# 224_distance.net
KiCad netlist of a schematic drawn in EAGLE
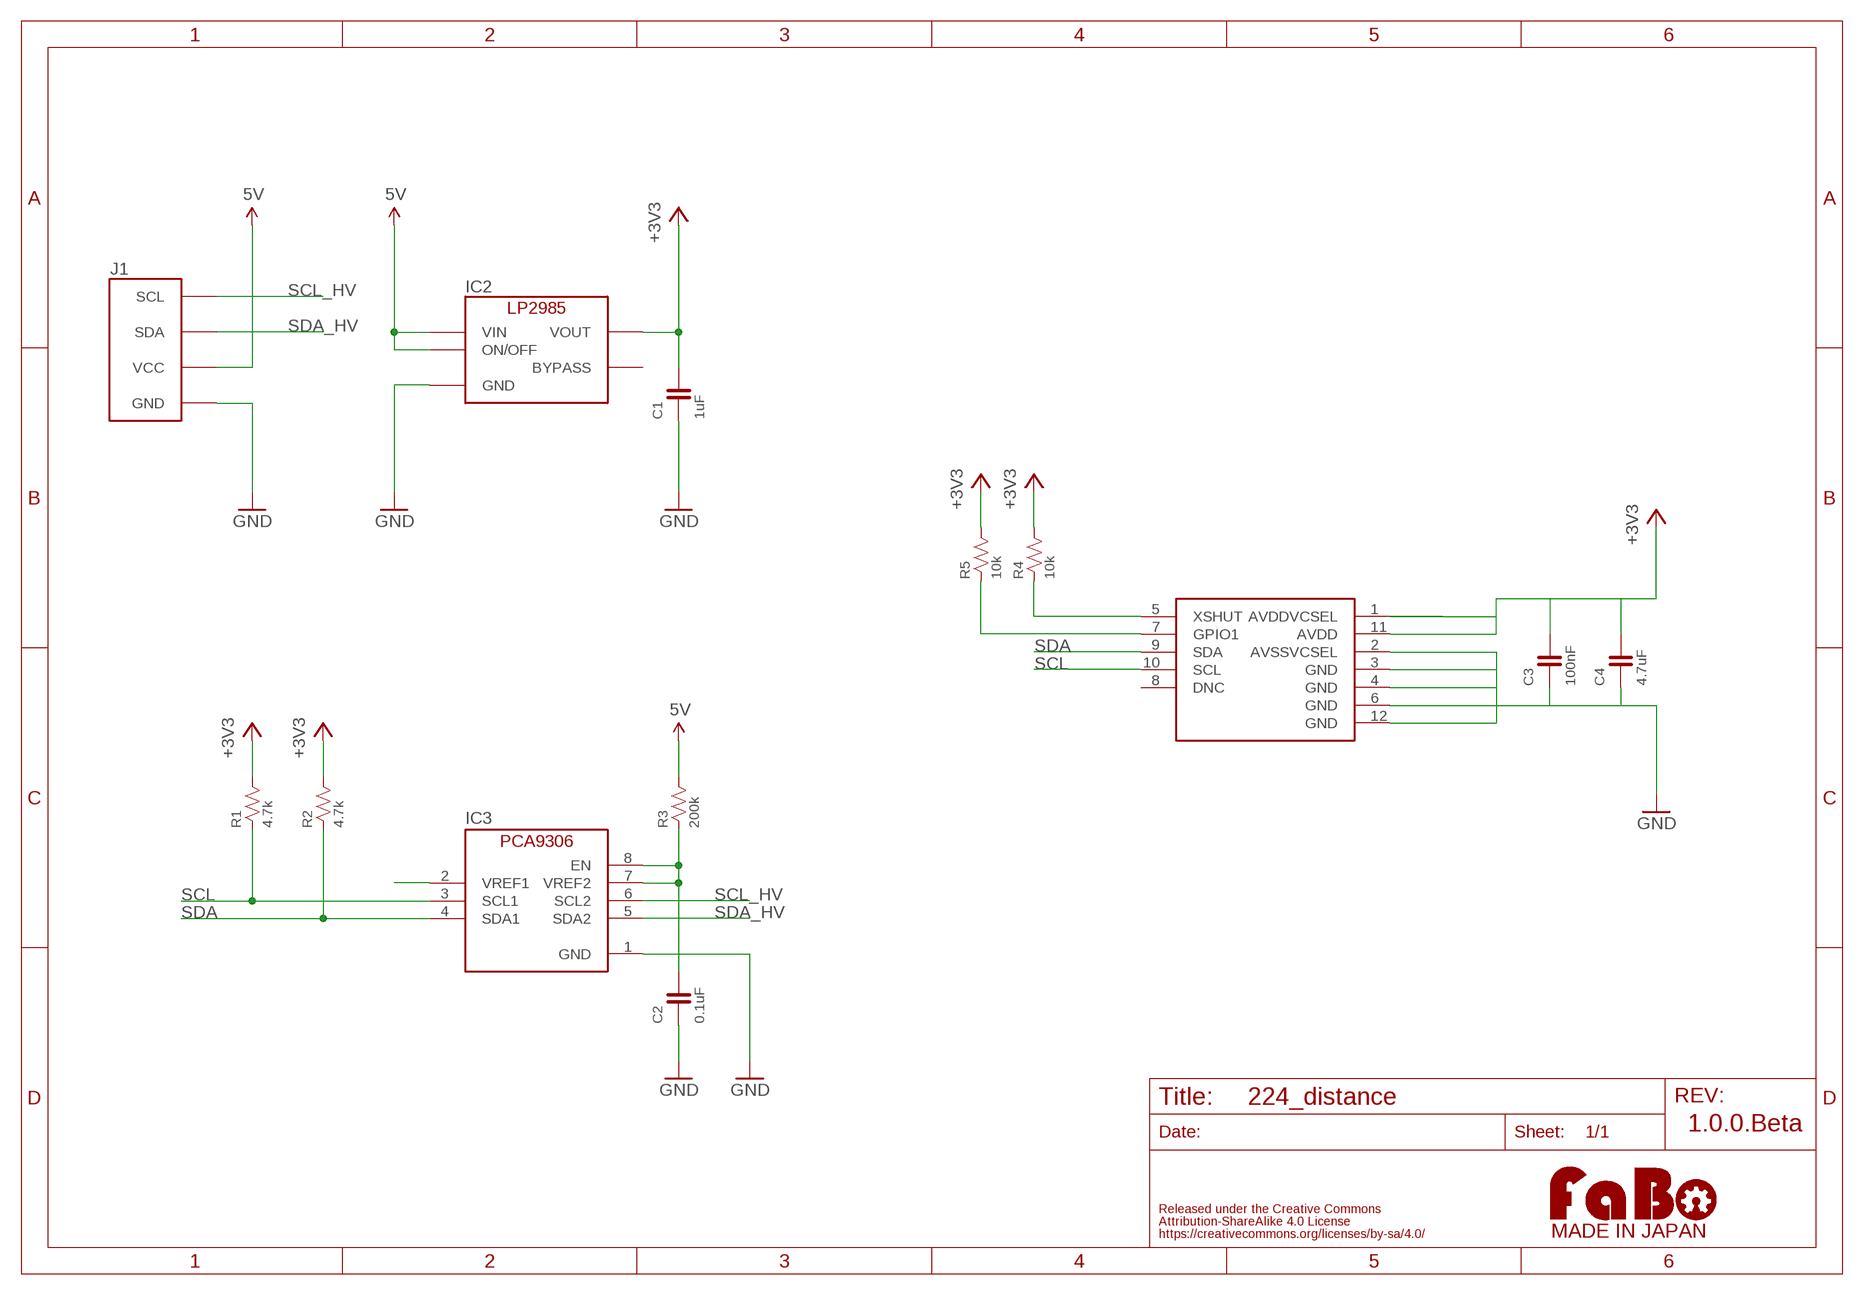
[diagram p0: schematic, sheet 1]

(export (version "E")
  (design (tool "Eeschema 10.0.6"))
  (components
    (comp (ref "C1")
      (value "1uF")
      (footprint "eagle-import:0603")
      (libsource (lib "eagle-import") (part "CAPACITOR-0603"))
    )
    (comp (ref "C2")
      (value "0.1uF")
      (footprint "eagle-import:0603")
      (libsource (lib "eagle-import") (part "CAPACITOR-0603"))
    )
    (comp (ref "C3")
      (value "100nF")
      (footprint "eagle-import:0603")
      (libsource (lib "eagle-import") (part "CAPACITOR-0603"))
    )
    (comp (ref "C4")
      (value "4.7uF")
      (footprint "eagle-import:0603")
      (libsource (lib "eagle-import") (part "CAPACITOR-0603"))
    )
    (comp (ref "IC2")
      (value "LP2985-33DBV")
      (footprint "eagle-import:SOT-23-5")
      (libsource (lib "eagle-import") (part "LP2985-33DBV"))
    )
    (comp (ref "IC3")
      (value "PCA9306GM")
      (footprint "eagle-import:XQFN8")
      (libsource (lib "eagle-import") (part "PCA9306GM"))
    )
    (comp (ref "J1")
      (value "FABO_BRICK_I2C-S04B-PASK-2")
      (footprint "eagle-import:FABO_BRICK_I2C_S04B-PASK-2")
      (libsource (lib "eagle-import") (part "FABO_BRICK_I2C-S04B-PASK-2"))
    )
    (comp (ref "R1")
      (value "4.7k")
      (footprint "eagle-import:0603")
      (libsource (lib "eagle-import") (part "RESISTOR-0603"))
    )
    (comp (ref "R2")
      (value "4.7k")
      (footprint "eagle-import:0603")
      (libsource (lib "eagle-import") (part "RESISTOR-0603"))
    )
    (comp (ref "R3")
      (value "200k")
      (footprint "eagle-import:0603")
      (libsource (lib "eagle-import") (part "RESISTOR-0603"))
    )
    (comp (ref "R4")
      (value "10k")
      (footprint "eagle-import:0603")
      (libsource (lib "eagle-import") (part "RESISTOR-0603"))
    )
    (comp (ref "R5")
      (value "10k")
      (footprint "eagle-import:0603")
      (libsource (lib "eagle-import") (part "RESISTOR-0603"))
    )
    (comp (ref "U$3")
      (value "LOGO_FABO-M")
      (footprint "eagle-import:LOGO_FABO_MS")
      (libsource (lib "eagle-import") (part "LOGO_FABO-M"))
    )
    (comp (ref "VL1")
      (value "ST-VL53L0XVL53")
      (footprint "eagle-import:ST-VL53L0X")
      (libsource (lib "eagle-import") (part "ST-VL53L0XVL53"))
    )
  )
  (nets
    (net (code "1") (name "+3V3") (class "Default")
      (node (ref "C1") (pin "2") (pinfunction "2_2") (pintype "passive"))
      (node (ref "C3") (pin "2") (pinfunction "2_2") (pintype "passive"))
      (node (ref "C4") (pin "2") (pinfunction "2_2") (pintype "passive"))
      (node (ref "IC2") (pin "5") (pinfunction "VOUT_5") (pintype "output"))
      (node (ref "R1") (pin "2") (pinfunction "2_2") (pintype "bidirectional"))
      (node (ref "R2") (pin "2") (pinfunction "2_2") (pintype "bidirectional"))
      (node (ref "R4") (pin "2") (pinfunction "2_2") (pintype "bidirectional"))
      (node (ref "R5") (pin "2") (pinfunction "2_2") (pintype "bidirectional"))
      (node (ref "VL1") (pin "1") (pinfunction "AVDDVCSEL_1") (pintype "bidirectional"))
      (node (ref "VL1") (pin "11") (pinfunction "AVDD_11") (pintype "bidirectional"))
    )
    (net (code "2") (name "/SCL") (class "Default")
      (node (ref "IC3") (pin "3") (pinfunction "SCL1_3") (pintype "bidirectional"))
      (node (ref "R1") (pin "1") (pinfunction "1_1") (pintype "bidirectional"))
      (node (ref "VL1") (pin "10") (pinfunction "SCL_10") (pintype "bidirectional"))
    )
    (net (code "3") (name "/SCL_HV") (class "Default")
      (node (ref "IC3") (pin "6") (pinfunction "SCL2_6") (pintype "bidirectional"))
      (node (ref "J1") (pin "SCL") (pinfunction "SCL_SCL") (pintype "bidirectional"))
    )
    (net (code "4") (name "/SDA") (class "Default")
      (node (ref "IC3") (pin "4") (pinfunction "SDA1_4") (pintype "bidirectional"))
      (node (ref "R2") (pin "1") (pinfunction "1_1") (pintype "bidirectional"))
      (node (ref "VL1") (pin "9") (pinfunction "SDA_9") (pintype "bidirectional"))
    )
    (net (code "5") (name "/SDA_HV") (class "Default")
      (node (ref "IC3") (pin "5") (pinfunction "SDA2_5") (pintype "bidirectional"))
      (node (ref "J1") (pin "SDA") (pinfunction "SDA_SDA") (pintype "bidirectional"))
    )
    (net (code "6") (name "5V") (class "Default")
      (node (ref "IC2") (pin "1") (pinfunction "VIN_1") (pintype "input"))
      (node (ref "IC2") (pin "3") (pinfunction "ON/OFF_3") (pintype "input"))
      (node (ref "J1") (pin "VCC") (pinfunction "VCC_VCC") (pintype "bidirectional"))
      (node (ref "R3") (pin "2") (pinfunction "2_2") (pintype "bidirectional"))
    )
    (net (code "7") (name "GND") (class "Default")
      (node (ref "C1") (pin "1") (pinfunction "1_1") (pintype "passive"))
      (node (ref "C2") (pin "1") (pinfunction "1_1") (pintype "passive"))
      (node (ref "C3") (pin "1") (pinfunction "1_1") (pintype "passive"))
      (node (ref "C4") (pin "1") (pinfunction "1_1") (pintype "passive"))
      (node (ref "IC2") (pin "2") (pinfunction "GND_2") (pintype "power_in"))
      (node (ref "IC3") (pin "1") (pinfunction "GND_1") (pintype "bidirectional"))
      (node (ref "J1") (pin "GND") (pinfunction "GND_GND") (pintype "bidirectional"))
      (node (ref "VL1") (pin "12") (pinfunction "GND_12") (pintype "bidirectional"))
      (node (ref "VL1") (pin "2") (pinfunction "AVSSVCSEL_2") (pintype "bidirectional"))
      (node (ref "VL1") (pin "3") (pinfunction "GND_3") (pintype "bidirectional"))
      (node (ref "VL1") (pin "4") (pinfunction "GND_4") (pintype "bidirectional"))
      (node (ref "VL1") (pin "6") (pinfunction "GND_6") (pintype "bidirectional"))
    )
    (net (code "8") (name "Net-(IC3-EN)") (class "Default")
      (node (ref "C2") (pin "2") (pinfunction "2_2") (pintype "passive"))
      (node (ref "IC3") (pin "7") (pinfunction "VREF2_7") (pintype "bidirectional"))
      (node (ref "IC3") (pin "8") (pinfunction "EN_8") (pintype "bidirectional"))
      (node (ref "R3") (pin "1") (pinfunction "1_1") (pintype "bidirectional"))
    )
    (net (code "9") (name "Net-(VL1-GPIO1)") (class "Default")
      (node (ref "R5") (pin "1") (pinfunction "1_1") (pintype "bidirectional"))
      (node (ref "VL1") (pin "7") (pinfunction "GPIO1_7") (pintype "bidirectional"))
    )
    (net (code "10") (name "Net-(VL1-XSHUT)") (class "Default")
      (node (ref "R4") (pin "1") (pinfunction "1_1") (pintype "bidirectional"))
      (node (ref "VL1") (pin "5") (pinfunction "XSHUT_5") (pintype "bidirectional"))
    )
    (net (code "11") (name "unconnected-(IC2-BYPASS-Pad4)") (class "Default")
      (node (ref "IC2") (pin "4") (pinfunction "BYPASS_4") (pintype "bidirectional"))
    )
    (net (code "12") (name "unconnected-(IC3-VREF1-Pad2)") (class "Default")
      (node (ref "IC3") (pin "2") (pinfunction "VREF1_2") (pintype "bidirectional"))
    )
    (net (code "13") (name "unconnected-(VL1-DNC-Pad8)") (class "Default")
      (node (ref "VL1") (pin "8") (pinfunction "DNC_8") (pintype "bidirectional"))
    )
  )
)
